# nRF52832_qfaa_dcdc.net
KiCad netlist of a schematic drawn in EAGLE
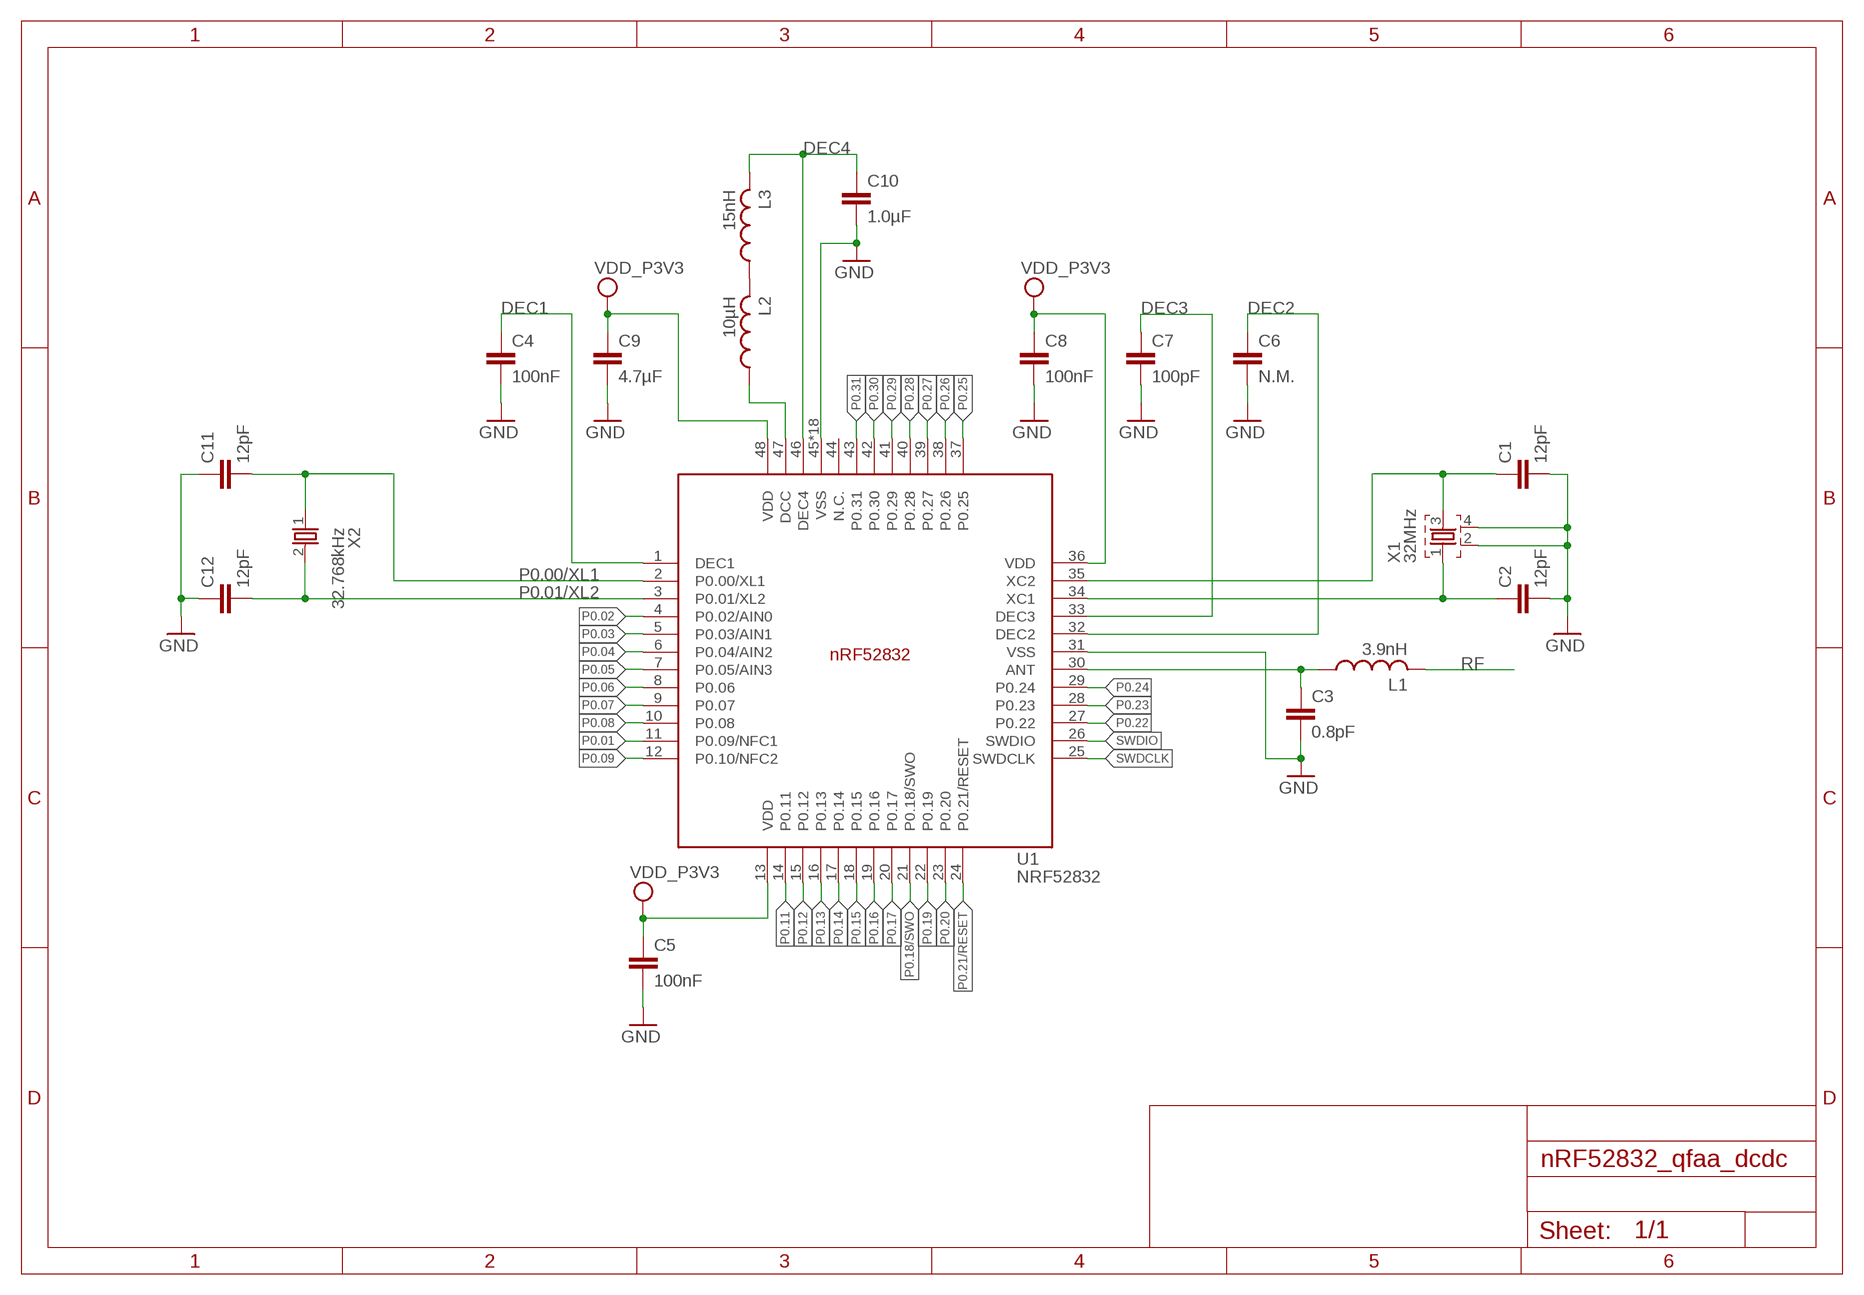
[diagram p0: schematic, sheet 1]

(export (version "E")
  (design (tool "Eeschema 10.0.6"))
  (components
    (comp (ref "C1")
      (value "12pF")
      (footprint "eagle-import:RESC0402_N")
      (libsource (lib "eagle-import") (part "CAPACITOR_0402_N"))
    )
    (comp (ref "C2")
      (value "12pF")
      (footprint "eagle-import:RESC0402_N")
      (libsource (lib "eagle-import") (part "CAPACITOR_0402_N"))
    )
    (comp (ref "C3")
      (value "0.8pF")
      (footprint "eagle-import:RESC0402_N")
      (libsource (lib "eagle-import") (part "CAPACITOR_0402_N"))
    )
    (comp (ref "C4")
      (value "100nF")
      (footprint "eagle-import:RESC0402_N")
      (libsource (lib "eagle-import") (part "CAPACITOR_0402_N"))
    )
    (comp (ref "C5")
      (value "100nF")
      (footprint "eagle-import:RESC0402_N")
      (libsource (lib "eagle-import") (part "CAPACITOR_0402_N"))
    )
    (comp (ref "C6")
      (value "N.M.")
      (footprint "eagle-import:RESC0402_N")
      (libsource (lib "eagle-import") (part "CAPACITOR_0402_N"))
    )
    (comp (ref "C7")
      (value "100pF")
      (footprint "eagle-import:RESC0402_N")
      (libsource (lib "eagle-import") (part "CAPACITOR_0402_N"))
    )
    (comp (ref "C8")
      (value "100nF")
      (footprint "eagle-import:RESC0402_N")
      (libsource (lib "eagle-import") (part "CAPACITOR_0402_N"))
    )
    (comp (ref "C9")
      (value "4.7µF")
      (footprint "eagle-import:RESC0603_N")
      (libsource (lib "eagle-import") (part "CAPACITOR_0603_N"))
    )
    (comp (ref "C10")
      (value "1.0µF")
      (footprint "eagle-import:RESC0603_N")
      (libsource (lib "eagle-import") (part "CAPACITOR_0603_N"))
    )
    (comp (ref "C11")
      (value "12pF")
      (footprint "eagle-import:RESC0402_N")
      (libsource (lib "eagle-import") (part "CAPACITOR_0402_N"))
    )
    (comp (ref "C12")
      (value "12pF")
      (footprint "eagle-import:RESC0402_N")
      (libsource (lib "eagle-import") (part "CAPACITOR_0402_N"))
    )
    (comp (ref "L1")
      (value "3.9nH")
      (footprint "eagle-import:RESC0402_N")
      (libsource (lib "eagle-import") (part "INDUCTOR_0402_N"))
    )
    (comp (ref "L2")
      (value "10µH")
      (footprint "eagle-import:RESC0603_N")
      (libsource (lib "eagle-import") (part "INDUCTOR_0603_N"))
    )
    (comp (ref "L3")
      (value "15nH")
      (footprint "eagle-import:RESC0402_N")
      (libsource (lib "eagle-import") (part "INDUCTOR_0402_N"))
    )
    (comp (ref "U1")
      (value "NRF52832")
      (footprint "eagle-import:QFN40P600X600X90-48_N")
      (libsource (lib "eagle-import") (part "NRF52832"))
    )
    (comp (ref "X1")
      (value "32MHz")
      (footprint "eagle-import:BT-XTAL_2016_N")
      (libsource (lib "eagle-import") (part "XTAL_32MHZ"))
    )
    (comp (ref "X2")
      (value "32.768kHz")
      (footprint "eagle-import:XTAL_3215_N")
      (libsource (lib "eagle-import") (part "XTAL_32KHZ"))
    )
  )
  (nets
    (net (code "1") (name "/DEC1") (class "Default")
      (node (ref "C4") (pin "1") (pinfunction "1_1") (pintype "passive"))
      (node (ref "U1") (pin "1") (pinfunction "DEC1_1") (pintype "power_in"))
    )
    (net (code "2") (name "/DEC2") (class "Default")
      (node (ref "C6") (pin "1") (pinfunction "1_1") (pintype "passive"))
      (node (ref "U1") (pin "32") (pinfunction "DEC2_32") (pintype "bidirectional"))
    )
    (net (code "3") (name "/DEC3") (class "Default")
      (node (ref "C7") (pin "1") (pinfunction "1_1") (pintype "passive"))
      (node (ref "U1") (pin "33") (pinfunction "DEC3_33") (pintype "bidirectional"))
    )
    (net (code "4") (name "/DEC4") (class "Default")
      (node (ref "C10") (pin "1") (pinfunction "1_1") (pintype "passive"))
      (node (ref "L3") (pin "2") (pinfunction "2_2") (pintype "passive"))
      (node (ref "U1") (pin "46") (pinfunction "DEC4_46") (pintype "power_in"))
    )
    (net (code "5") (name "/P0.00{slash}XL1") (class "Default")
      (node (ref "C11") (pin "2") (pinfunction "2_2") (pintype "passive"))
      (node (ref "U1") (pin "2") (pinfunction "P0.00/XL1_2") (pintype "bidirectional"))
      (node (ref "X2") (pin "1") (pinfunction "1_1") (pintype "passive"))
    )
    (net (code "6") (name "/P0.01{slash}XL2") (class "Default")
      (node (ref "C12") (pin "2") (pinfunction "2_2") (pintype "passive"))
      (node (ref "U1") (pin "3") (pinfunction "P0.01/XL2_3") (pintype "bidirectional"))
      (node (ref "X2") (pin "2") (pinfunction "2_2") (pintype "passive"))
    )
    (net (code "7") (name "/RF") (class "Default")
      (node (ref "L1") (pin "2") (pinfunction "2_2") (pintype "passive"))
    )
    (net (code "8") (name "GND") (class "Default")
      (node (ref "C1") (pin "2") (pinfunction "2_2") (pintype "passive"))
      (node (ref "C10") (pin "2") (pinfunction "2_2") (pintype "passive"))
      (node (ref "C11") (pin "1") (pinfunction "1_1") (pintype "passive"))
      (node (ref "C12") (pin "1") (pinfunction "1_1") (pintype "passive"))
      (node (ref "C2") (pin "2") (pinfunction "2_2") (pintype "passive"))
      (node (ref "C3") (pin "2") (pinfunction "2_2") (pintype "passive"))
      (node (ref "C4") (pin "2") (pinfunction "2_2") (pintype "passive"))
      (node (ref "C5") (pin "2") (pinfunction "2_2") (pintype "passive"))
      (node (ref "C6") (pin "2") (pinfunction "2_2") (pintype "passive"))
      (node (ref "C7") (pin "2") (pinfunction "2_2") (pintype "passive"))
      (node (ref "C8") (pin "2") (pinfunction "2_2") (pintype "passive"))
      (node (ref "C9") (pin "2") (pinfunction "2_2") (pintype "passive"))
      (node (ref "U1") (pin "31") (pinfunction "VSS_31") (pintype "bidirectional"))
      (node (ref "U1") (pin "45") (pinfunction "VSS_45") (pintype "power_in"))
      (node (ref "U1") (pin "PAD") (pinfunction "VSS_PAD") (pintype "power_in"))
      (node (ref "U1") (pin "PAD@VIA01") (pinfunction "VSS_PAD@VIA01") (pintype "power_in"))
      (node (ref "U1") (pin "PAD@VIA02") (pinfunction "VSS_PAD@VIA02") (pintype "power_in"))
      (node (ref "U1") (pin "PAD@VIA03") (pinfunction "VSS_PAD@VIA03") (pintype "power_in"))
      (node (ref "U1") (pin "PAD@VIA04") (pinfunction "VSS_PAD@VIA04") (pintype "power_in"))
      (node (ref "U1") (pin "PAD@VIA05") (pinfunction "VSS_PAD@VIA05") (pintype "power_in"))
      (node (ref "U1") (pin "PAD@VIA06") (pinfunction "VSS_PAD@VIA06") (pintype "power_in"))
      (node (ref "U1") (pin "PAD@VIA07") (pinfunction "VSS_PAD@VIA07") (pintype "power_in"))
      (node (ref "U1") (pin "PAD@VIA08") (pinfunction "VSS_PAD@VIA08") (pintype "power_in"))
      (node (ref "U1") (pin "PAD@VIA09") (pinfunction "VSS_PAD@VIA09") (pintype "power_in"))
      (node (ref "U1") (pin "PAD@VIA10") (pinfunction "VSS_PAD@VIA10") (pintype "power_in"))
      (node (ref "U1") (pin "PAD@VIA11") (pinfunction "VSS_PAD@VIA11") (pintype "power_in"))
      (node (ref "U1") (pin "PAD@VIA12") (pinfunction "VSS_PAD@VIA12") (pintype "power_in"))
      (node (ref "U1") (pin "PAD@VIA13") (pinfunction "VSS_PAD@VIA13") (pintype "power_in"))
      (node (ref "U1") (pin "PAD@VIA14") (pinfunction "VSS_PAD@VIA14") (pintype "power_in"))
      (node (ref "U1") (pin "PAD@VIA15") (pinfunction "VSS_PAD@VIA15") (pintype "power_in"))
      (node (ref "U1") (pin "PAD@VIA16") (pinfunction "VSS_PAD@VIA16") (pintype "power_in"))
      (node (ref "X1") (pin "2") (pinfunction "2_2") (pintype "passive"))
      (node (ref "X1") (pin "4") (pinfunction "4_4") (pintype "passive"))
    )
    (net (code "9") (name "Net-(L2-Pad2)") (class "Default")
      (node (ref "L2") (pin "2") (pinfunction "2_2") (pintype "passive"))
      (node (ref "L3") (pin "1") (pinfunction "1_1") (pintype "passive"))
    )
    (net (code "10") (name "Net-(U1-ANT)") (class "Default")
      (node (ref "C3") (pin "1") (pinfunction "1_1") (pintype "passive"))
      (node (ref "L1") (pin "1") (pinfunction "1_1") (pintype "passive"))
      (node (ref "U1") (pin "30") (pinfunction "ANT_30") (pintype "bidirectional"))
    )
    (net (code "11") (name "Net-(U1-DCC)") (class "Default")
      (node (ref "L2") (pin "1") (pinfunction "1_1") (pintype "passive"))
      (node (ref "U1") (pin "47") (pinfunction "DCC_47") (pintype "output"))
    )
    (net (code "12") (name "Net-(U1-XC1)") (class "Default")
      (node (ref "C2") (pin "1") (pinfunction "1_1") (pintype "passive"))
      (node (ref "U1") (pin "34") (pinfunction "XC1_34") (pintype "input"))
      (node (ref "X1") (pin "1") (pinfunction "1_1") (pintype "passive"))
    )
    (net (code "13") (name "Net-(U1-XC2)") (class "Default")
      (node (ref "C1") (pin "1") (pinfunction "1_1") (pintype "passive"))
      (node (ref "U1") (pin "35") (pinfunction "XC2_35") (pintype "output"))
      (node (ref "X1") (pin "3") (pinfunction "3_3") (pintype "passive"))
    )
    (net (code "14") (name "P0.01") (class "Default")
      (node (ref "U1") (pin "11") (pinfunction "P0.09/NFC1_11") (pintype "bidirectional"))
    )
    (net (code "15") (name "P0.02") (class "Default")
      (node (ref "U1") (pin "4") (pinfunction "P0.02/AIN0_4") (pintype "bidirectional"))
    )
    (net (code "16") (name "P0.03") (class "Default")
      (node (ref "U1") (pin "5") (pinfunction "P0.03/AIN1_5") (pintype "bidirectional"))
    )
    (net (code "17") (name "P0.04") (class "Default")
      (node (ref "U1") (pin "6") (pinfunction "P0.04/AIN2_6") (pintype "bidirectional"))
    )
    (net (code "18") (name "P0.05") (class "Default")
      (node (ref "U1") (pin "7") (pinfunction "P0.05/AIN3_7") (pintype "bidirectional"))
    )
    (net (code "19") (name "P0.06") (class "Default")
      (node (ref "U1") (pin "8") (pinfunction "P0.06_8") (pintype "bidirectional"))
    )
    (net (code "20") (name "P0.07") (class "Default")
      (node (ref "U1") (pin "9") (pinfunction "P0.07_9") (pintype "bidirectional"))
    )
    (net (code "21") (name "P0.08") (class "Default")
      (node (ref "U1") (pin "10") (pinfunction "P0.08_10") (pintype "bidirectional"))
    )
    (net (code "22") (name "P0.09") (class "Default")
      (node (ref "U1") (pin "12") (pinfunction "P0.10/NFC2_12") (pintype "bidirectional"))
    )
    (net (code "23") (name "P0.11") (class "Default")
      (node (ref "U1") (pin "14") (pinfunction "P0.11_14") (pintype "bidirectional"))
    )
    (net (code "24") (name "P0.12") (class "Default")
      (node (ref "U1") (pin "15") (pinfunction "P0.12_15") (pintype "bidirectional"))
    )
    (net (code "25") (name "P0.13") (class "Default")
      (node (ref "U1") (pin "16") (pinfunction "P0.13_16") (pintype "bidirectional"))
    )
    (net (code "26") (name "P0.14") (class "Default")
      (node (ref "U1") (pin "17") (pinfunction "P0.14_17") (pintype "bidirectional"))
    )
    (net (code "27") (name "P0.15") (class "Default")
      (node (ref "U1") (pin "18") (pinfunction "P0.15_18") (pintype "bidirectional"))
    )
    (net (code "28") (name "P0.16") (class "Default")
      (node (ref "U1") (pin "19") (pinfunction "P0.16_19") (pintype "bidirectional"))
    )
    (net (code "29") (name "P0.17") (class "Default")
      (node (ref "U1") (pin "20") (pinfunction "P0.17_20") (pintype "bidirectional"))
    )
    (net (code "30") (name "P0.18{slash}SWO") (class "Default")
      (node (ref "U1") (pin "21") (pinfunction "P0.18/SWO_21") (pintype "bidirectional"))
    )
    (net (code "31") (name "P0.19") (class "Default")
      (node (ref "U1") (pin "22") (pinfunction "P0.19_22") (pintype "bidirectional"))
    )
    (net (code "32") (name "P0.20") (class "Default")
      (node (ref "U1") (pin "23") (pinfunction "P0.20_23") (pintype "bidirectional"))
    )
    (net (code "33") (name "P0.21{slash}RESET") (class "Default")
      (node (ref "U1") (pin "24") (pinfunction "P0.21/RESET_24") (pintype "bidirectional"))
    )
    (net (code "34") (name "P0.22") (class "Default")
      (node (ref "U1") (pin "27") (pinfunction "P0.22_27") (pintype "bidirectional"))
    )
    (net (code "35") (name "P0.23") (class "Default")
      (node (ref "U1") (pin "28") (pinfunction "P0.23_28") (pintype "bidirectional"))
    )
    (net (code "36") (name "P0.24") (class "Default")
      (node (ref "U1") (pin "29") (pinfunction "P0.24_29") (pintype "bidirectional"))
    )
    (net (code "37") (name "P0.25") (class "Default")
      (node (ref "U1") (pin "37") (pinfunction "P0.25_37") (pintype "bidirectional"))
    )
    (net (code "38") (name "P0.26") (class "Default")
      (node (ref "U1") (pin "38") (pinfunction "P0.26_38") (pintype "bidirectional"))
    )
    (net (code "39") (name "P0.27") (class "Default")
      (node (ref "U1") (pin "39") (pinfunction "P0.27_39") (pintype "bidirectional"))
    )
    (net (code "40") (name "P0.28") (class "Default")
      (node (ref "U1") (pin "40") (pinfunction "P0.28_40") (pintype "bidirectional"))
    )
    (net (code "41") (name "P0.29") (class "Default")
      (node (ref "U1") (pin "41") (pinfunction "P0.29_41") (pintype "bidirectional"))
    )
    (net (code "42") (name "P0.30") (class "Default")
      (node (ref "U1") (pin "42") (pinfunction "P0.30_42") (pintype "bidirectional"))
    )
    (net (code "43") (name "P0.31") (class "Default")
      (node (ref "U1") (pin "43") (pinfunction "P0.31_43") (pintype "bidirectional"))
    )
    (net (code "44") (name "SWDCLK") (class "Default")
      (node (ref "U1") (pin "25") (pinfunction "SWDCLK_25") (pintype "input"))
    )
    (net (code "45") (name "SWDIO") (class "Default")
      (node (ref "U1") (pin "26") (pinfunction "SWDIO_26") (pintype "bidirectional"))
    )
    (net (code "46") (name "VDD_P3V3") (class "Default")
      (node (ref "C5") (pin "1") (pinfunction "1_1") (pintype "passive"))
      (node (ref "C8") (pin "1") (pinfunction "1_1") (pintype "passive"))
      (node (ref "C9") (pin "1") (pinfunction "1_1") (pintype "passive"))
      (node (ref "U1") (pin "13") (pinfunction "VDD_13") (pintype "power_in"))
      (node (ref "U1") (pin "36") (pinfunction "VDD_36") (pintype "power_in"))
      (node (ref "U1") (pin "48") (pinfunction "VDD_48") (pintype "power_in"))
    )
    (net (code "47") (name "unconnected-(U1-N.C.-Pad44)") (class "Default")
      (node (ref "U1") (pin "44") (pinfunction "N.C._44") (pintype "no_connect"))
    )
  )
)
